# SCH.net
KiCad netlist of a schematic drawn in EAGLE
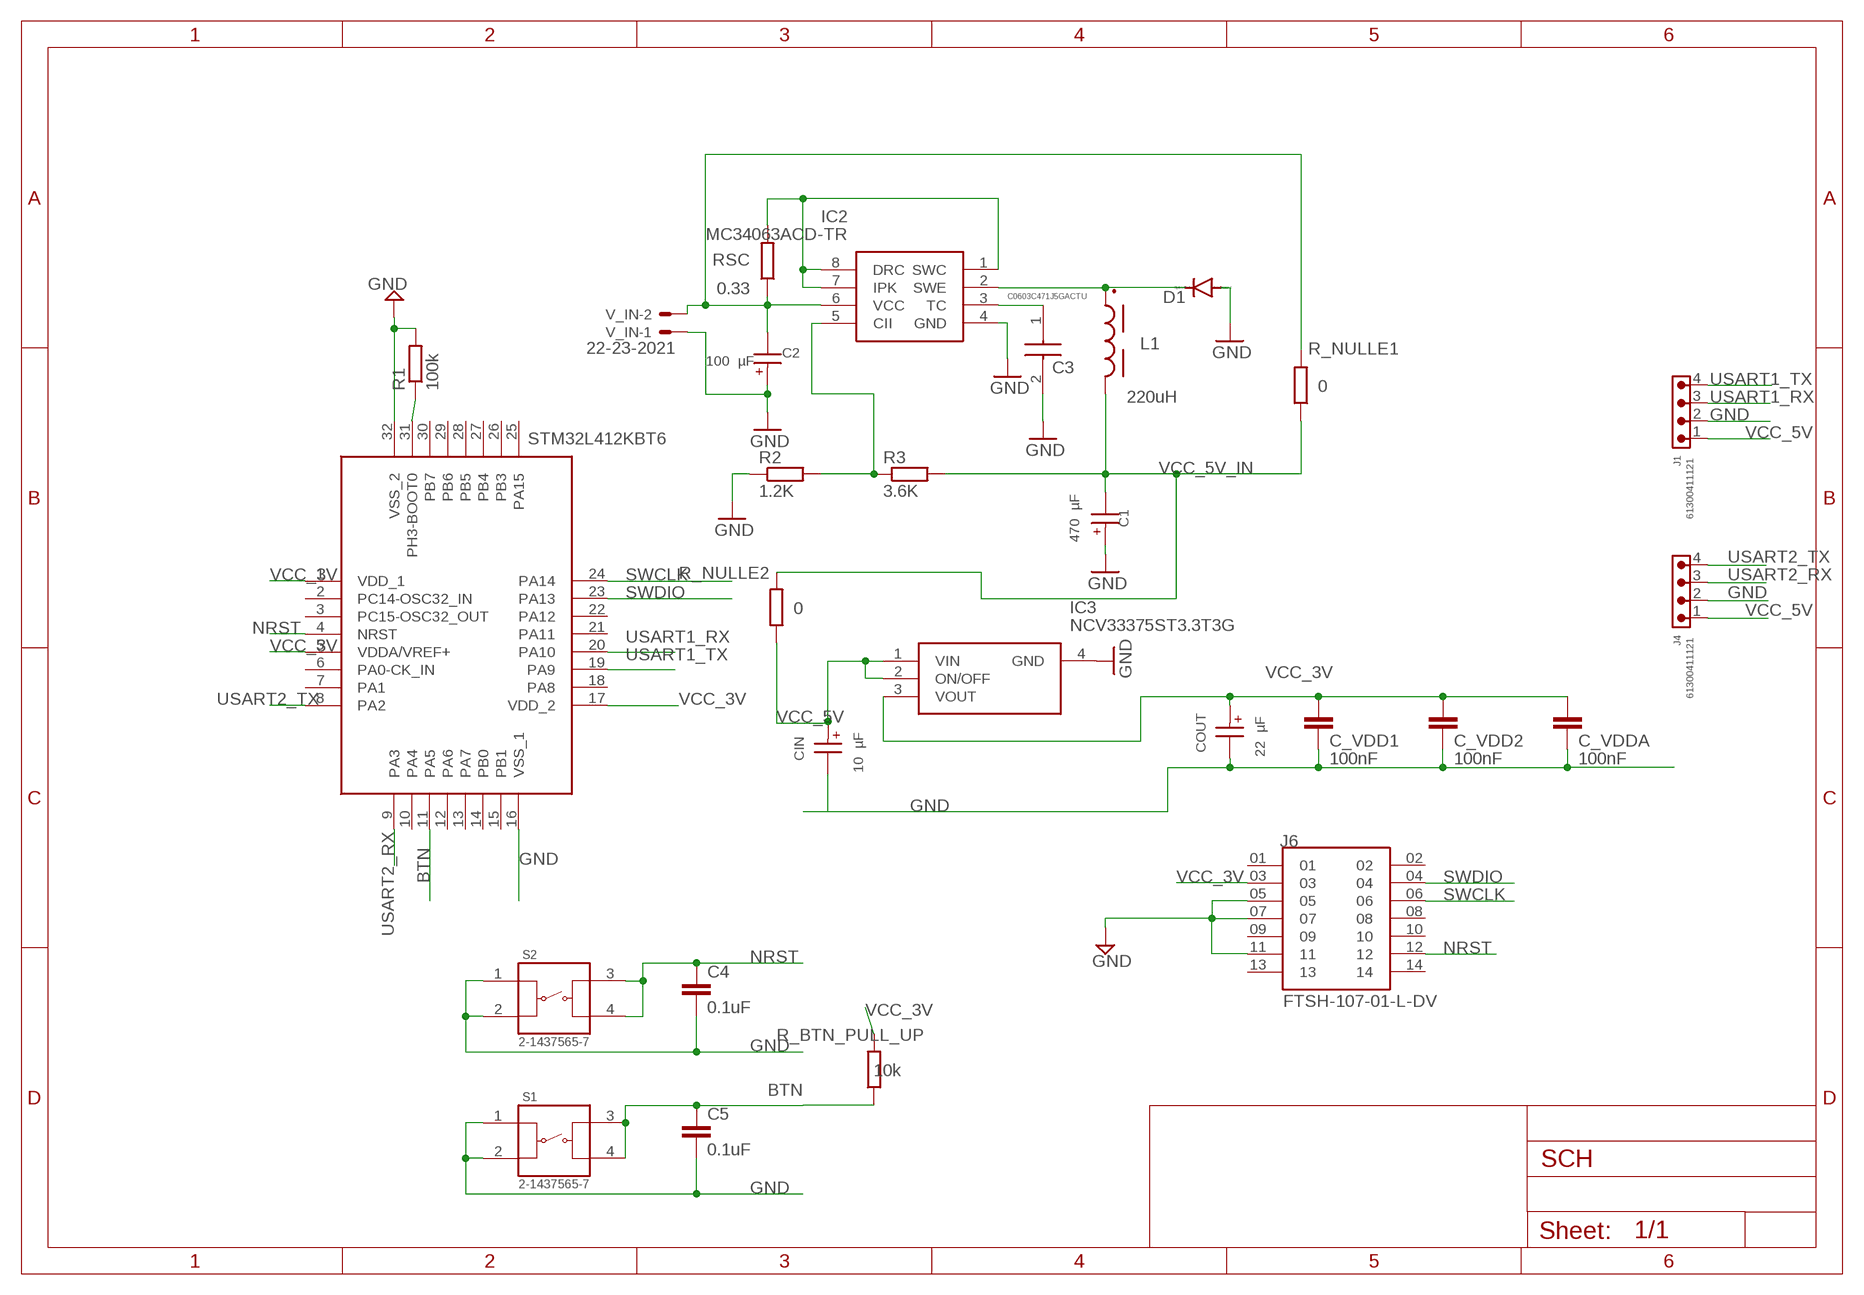
[diagram p0: schematic, sheet 1]

(export (version "E")
  (design (tool "Eeschema 10.0.6"))
  (components
    (comp (ref "C1")
      (value "470 µF")
      (footprint "eagle-import:WCAP-ASLL_8X10.5(DXL)")
      (libsource (lib "eagle-import") (part "WCAP-ASLL_8X10.5_865060353009"))
    )
    (comp (ref "C2")
      (value "100 µF")
      (footprint "eagle-import:WCAP-ASLL_6.3X7.7(DXL)")
      (libsource (lib "eagle-import") (part "WCAP-ASLL_6.3X7.7_865060445005"))
    )
    (comp (ref "C3")
      (value "C0603C471J5GACTU")
      (footprint "eagle-import:C0603")
      (fields (field (name "MOUSER_PART_NUMBER") "80-C0603C471J5G"))
      (libsource (lib "eagle-import") (part "C0603C471J5GACTU"))
    )
    (comp (ref "C4")
      (value "0.1uF")
      (footprint "eagle-import:C0603")
      (libsource (lib "eagle-import") (part "C-EUC0603"))
    )
    (comp (ref "C5")
      (value "0.1uF")
      (footprint "eagle-import:C0603")
      (libsource (lib "eagle-import") (part "C-EUC0603"))
    )
    (comp (ref "CIN")
      (value "10 µF")
      (footprint "eagle-import:WCAP-ASLL_4X5.5(DXL)")
      (libsource (lib "eagle-import") (part "WCAP-ASLL_4X5.5_865060440001"))
    )
    (comp (ref "COUT")
      (value "22 µF")
      (footprint "eagle-import:WCAP-ASLL_5X5.5(DXL)")
      (libsource (lib "eagle-import") (part "WCAP-ASLL_5X5.5_865060442002"))
    )
    (comp (ref "C_VDD1")
      (value "100nF")
      (footprint "eagle-import:C0603")
      (libsource (lib "eagle-import") (part "C-EUC0603"))
    )
    (comp (ref "C_VDD2")
      (value "100nF")
      (footprint "eagle-import:C0603")
      (libsource (lib "eagle-import") (part "C-EUC0603"))
    )
    (comp (ref "C_VDDA")
      (value "100nF")
      (footprint "eagle-import:C0603")
      (libsource (lib "eagle-import") (part "C-EUC0603"))
    )
    (comp (ref "D1")
      (value "DIODE-DO214AC")
      (footprint "eagle-import:DO214AC")
      (libsource (lib "eagle-import") (part "DIODE-DO214AC"))
    )
    (comp (ref "IC1")
      (value "STM32L412KBT6")
      (footprint "eagle-import:QFP80P900X900X160-32N")
      (fields (field (name "MOUSER_PART_NUMBER") "511-STM32L412KBT6"))
      (libsource (lib "eagle-import") (part "STM32L412KBT6"))
    )
    (comp (ref "IC2")
      (value "MC34063ACD-TR")
      (footprint "eagle-import:SOIC127P600X175-8N")
      (fields (field (name "MOUSER_PART_NUMBER") "511-MC34063ACD-TR"))
      (libsource (lib "eagle-import") (part "MC34063ACD-TR"))
    )
    (comp (ref "IC3")
      (value "NCV33375ST3.3T3G")
      (footprint "eagle-import:SOT230P700X175-4N")
      (fields (field (name "MOUSER_PART_NUMBER") "863-NCV33375ST3.3T3G"))
      (libsource (lib "eagle-import") (part "NCV33375ST3.3T3G"))
    )
    (comp (ref "J1")
      (value "61300411121")
      (footprint "eagle-import:61300411121")
      (libsource (lib "eagle-import") (part "6130XX11121_61300411121"))
    )
    (comp (ref "J4")
      (value "61300411121")
      (footprint "eagle-import:61300411121")
      (libsource (lib "eagle-import") (part "6130XX11121_61300411121"))
    )
    (comp (ref "J6")
      (value "FTSH-107-01-L-DV")
      (footprint "eagle-import:SAMTEC_FTSH-107-01-L-DV")
      (fields (field (name "MANUFACTURER") "Samtec"))
      (libsource (lib "eagle-import") (part "FTSH-107-01-L-DV"))
    )
    (comp (ref "L1")
      (value "220uH")
      (footprint "eagle-import:WE-PDA_1260")
      (libsource (lib "eagle-import") (part "WE-PDA_1260_784771221"))
    )
    (comp (ref "R1")
      (value "100k")
      (footprint "eagle-import:R0603")
      (libsource (lib "eagle-import") (part "R-EU_R0603"))
    )
    (comp (ref "R2")
      (value "1.2K")
      (footprint "eagle-import:R0603")
      (libsource (lib "eagle-import") (part "R-EU_R0603"))
    )
    (comp (ref "R3")
      (value "3.6K")
      (footprint "eagle-import:R0603")
      (libsource (lib "eagle-import") (part "R-EU_R0603"))
    )
    (comp (ref "RSC")
      (value "0.33")
      (footprint "eagle-import:R1206W")
      (libsource (lib "eagle-import") (part "R-EU_R1206W"))
    )
    (comp (ref "R_BTN_PULL_UP")
      (value "10k")
      (footprint "eagle-import:R0603")
      (libsource (lib "eagle-import") (part "R-EU_R0603"))
    )
    (comp (ref "R_NULLE1")
      (value "0")
      (footprint "eagle-import:R0603")
      (libsource (lib "eagle-import") (part "R-EU_R0603"))
    )
    (comp (ref "R_NULLE2")
      (value "0")
      (footprint "eagle-import:R0603")
      (libsource (lib "eagle-import") (part "R-EU_R0603"))
    )
    (comp (ref "S1")
      (value "2-1437565-7")
      (footprint "eagle-import:SW_2-1437565-7")
      (fields (field (name "MF") "TE Connectivity") (field (name "MP") "FSM2JSMA"))
      (libsource (lib "eagle-import") (part "2-1437565-7"))
    )
    (comp (ref "S2")
      (value "2-1437565-7")
      (footprint "eagle-import:SW_2-1437565-7")
      (fields (field (name "MF") "TE Connectivity") (field (name "MP") "FSM2JSMA"))
      (libsource (lib "eagle-import") (part "2-1437565-7"))
    )
    (comp (ref "V_IN")
      (value "22-23-2021")
      (footprint "eagle-import:22-23-2021")
      (fields (field (name "MF") "MOLEX"))
      (libsource (lib "eagle-import") (part "22-23-2021"))
    )
  )
  (nets
    (net (code "1") (name "/BTN") (class "Default")
      (node (ref "C5") (pin "1") (pinfunction "1_1") (pintype "passive"))
      (node (ref "IC1") (pin "11") (pinfunction "PA5_11") (pintype "bidirectional"))
      (node (ref "R_BTN_PULL_UP") (pin "1") (pinfunction "1_1") (pintype "passive"))
      (node (ref "S1") (pin "3") (pinfunction "3_3") (pintype "passive"))
      (node (ref "S1") (pin "4") (pinfunction "4_4") (pintype "passive"))
    )
    (net (code "2") (name "/NRST") (class "Default")
      (node (ref "C4") (pin "1") (pinfunction "1_1") (pintype "passive"))
      (node (ref "IC1") (pin "4") (pinfunction "NRST_4") (pintype "input"))
      (node (ref "J6") (pin "12") (pinfunction "12_12") (pintype "passive"))
      (node (ref "S2") (pin "3") (pinfunction "3_3") (pintype "passive"))
      (node (ref "S2") (pin "4") (pinfunction "4_4") (pintype "passive"))
    )
    (net (code "3") (name "/SWCLK") (class "Default")
      (node (ref "IC1") (pin "24") (pinfunction "PA14_24") (pintype "bidirectional"))
      (node (ref "J6") (pin "06") (pinfunction "06_06") (pintype "passive"))
    )
    (net (code "4") (name "/SWDIO") (class "Default")
      (node (ref "IC1") (pin "23") (pinfunction "PA13_23") (pintype "bidirectional"))
      (node (ref "J6") (pin "04") (pinfunction "04_04") (pintype "passive"))
    )
    (net (code "5") (name "/USART1_RX") (class "Default")
      (node (ref "IC1") (pin "20") (pinfunction "PA10_20") (pintype "bidirectional"))
      (node (ref "J1") (pin "3") (pinfunction "3_3") (pintype "passive"))
    )
    (net (code "6") (name "/USART1_TX") (class "Default")
      (node (ref "IC1") (pin "19") (pinfunction "PA9_19") (pintype "bidirectional"))
      (node (ref "J1") (pin "4") (pinfunction "4_4") (pintype "passive"))
    )
    (net (code "7") (name "/USART2_RX") (class "Default")
      (node (ref "IC1") (pin "9") (pinfunction "PA3_9") (pintype "bidirectional"))
      (node (ref "J4") (pin "3") (pinfunction "3_3") (pintype "passive"))
    )
    (net (code "8") (name "/USART2_TX") (class "Default")
      (node (ref "IC1") (pin "8") (pinfunction "PA2_8") (pintype "bidirectional"))
      (node (ref "J4") (pin "4") (pinfunction "4_4") (pintype "passive"))
    )
    (net (code "9") (name "/VCC_3V") (class "Default")
      (node (ref "COUT") (pin "1") (pinfunction "+_1") (pintype "passive"))
      (node (ref "C_VDD1") (pin "1") (pinfunction "1_1") (pintype "passive"))
      (node (ref "C_VDD2") (pin "1") (pinfunction "1_1") (pintype "passive"))
      (node (ref "C_VDDA") (pin "1") (pinfunction "1_1") (pintype "passive"))
      (node (ref "IC1") (pin "1") (pinfunction "VDD_1_1") (pintype "power_in"))
      (node (ref "IC1") (pin "17") (pinfunction "VDD_2_17") (pintype "power_in"))
      (node (ref "IC1") (pin "5") (pinfunction "VDDA/VREF+_5") (pintype "power_in"))
      (node (ref "IC3") (pin "3") (pinfunction "VOUT_3") (pintype "bidirectional"))
      (node (ref "J6") (pin "03") (pinfunction "03_03") (pintype "passive"))
      (node (ref "R_BTN_PULL_UP") (pin "2") (pinfunction "2_2") (pintype "passive"))
    )
    (net (code "10") (name "/VCC_5V") (class "Default")
      (node (ref "CIN") (pin "1") (pinfunction "+_1") (pintype "passive"))
      (node (ref "IC3") (pin "1") (pinfunction "VIN_1") (pintype "bidirectional"))
      (node (ref "IC3") (pin "2") (pinfunction "ON/OFF_2") (pintype "bidirectional"))
      (node (ref "J1") (pin "1") (pinfunction "1_1") (pintype "passive"))
      (node (ref "J4") (pin "1") (pinfunction "1_1") (pintype "passive"))
      (node (ref "R_NULLE2") (pin "1") (pinfunction "1_1") (pintype "passive"))
    )
    (net (code "11") (name "/VCC_5V_IN") (class "Default")
      (node (ref "C1") (pin "2") (pinfunction "-_2") (pintype "passive"))
      (node (ref "L1") (pin "2") (pinfunction "2_2") (pintype "passive"))
      (node (ref "R3") (pin "2") (pinfunction "2_2") (pintype "passive"))
      (node (ref "R_NULLE1") (pin "1") (pinfunction "1_1") (pintype "passive"))
      (node (ref "R_NULLE2") (pin "2") (pinfunction "2_2") (pintype "passive"))
    )
    (net (code "12") (name "GND") (class "Default")
      (node (ref "C1") (pin "1") (pinfunction "+_1") (pintype "passive"))
      (node (ref "C2") (pin "1") (pinfunction "+_1") (pintype "passive"))
      (node (ref "C3") (pin "2") (pinfunction "2_2") (pintype "bidirectional"))
      (node (ref "C4") (pin "2") (pinfunction "2_2") (pintype "passive"))
      (node (ref "C5") (pin "2") (pinfunction "2_2") (pintype "passive"))
      (node (ref "CIN") (pin "2") (pinfunction "-_2") (pintype "passive"))
      (node (ref "COUT") (pin "2") (pinfunction "-_2") (pintype "passive"))
      (node (ref "C_VDD1") (pin "2") (pinfunction "2_2") (pintype "passive"))
      (node (ref "C_VDD2") (pin "2") (pinfunction "2_2") (pintype "passive"))
      (node (ref "C_VDDA") (pin "2") (pinfunction "2_2") (pintype "passive"))
      (node (ref "D1") (pin "A") (pinfunction "A_A") (pintype "passive"))
      (node (ref "IC1") (pin "16") (pinfunction "VSS_1_16") (pintype "power_in"))
      (node (ref "IC1") (pin "32") (pinfunction "VSS_2_32") (pintype "power_in"))
      (node (ref "IC2") (pin "4") (pinfunction "GND_4") (pintype "bidirectional"))
      (node (ref "IC3") (pin "4") (pinfunction "GND_4") (pintype "bidirectional"))
      (node (ref "J1") (pin "2") (pinfunction "2_2") (pintype "passive"))
      (node (ref "J4") (pin "2") (pinfunction "2_2") (pintype "passive"))
      (node (ref "J6") (pin "05") (pinfunction "05_05") (pintype "passive"))
      (node (ref "J6") (pin "07") (pinfunction "07_07") (pintype "passive"))
      (node (ref "J6") (pin "11") (pinfunction "11_11") (pintype "passive"))
      (node (ref "R1") (pin "2") (pinfunction "2_2") (pintype "passive"))
      (node (ref "R2") (pin "1") (pinfunction "1_1") (pintype "passive"))
      (node (ref "S1") (pin "1") (pinfunction "1_1") (pintype "passive"))
      (node (ref "S1") (pin "2") (pinfunction "2_2") (pintype "passive"))
      (node (ref "S2") (pin "1") (pinfunction "1_1") (pintype "passive"))
      (node (ref "S2") (pin "2") (pinfunction "2_2") (pintype "passive"))
      (node (ref "V_IN") (pin "1") (pinfunction "S_1") (pintype "passive"))
    )
    (net (code "13") (name "Net-(C2--)") (class "Default")
      (node (ref "C2") (pin "2") (pinfunction "-_2") (pintype "passive"))
      (node (ref "IC2") (pin "6") (pinfunction "VCC_6") (pintype "bidirectional"))
      (node (ref "RSC") (pin "1") (pinfunction "1_1") (pintype "passive"))
      (node (ref "R_NULLE1") (pin "2") (pinfunction "2_2") (pintype "passive"))
      (node (ref "V_IN") (pin "2") (pinfunction "S_2") (pintype "passive"))
    )
    (net (code "14") (name "Net-(IC1-PH3-BOOT0)") (class "Default")
      (node (ref "IC1") (pin "31") (pinfunction "PH3-BOOT0_31") (pintype "bidirectional"))
      (node (ref "R1") (pin "1") (pinfunction "1_1") (pintype "passive"))
    )
    (net (code "15") (name "Net-(IC2-CII)") (class "Default")
      (node (ref "IC2") (pin "5") (pinfunction "CII_5") (pintype "bidirectional"))
      (node (ref "R2") (pin "2") (pinfunction "2_2") (pintype "passive"))
      (node (ref "R3") (pin "1") (pinfunction "1_1") (pintype "passive"))
    )
    (net (code "16") (name "Net-(IC2-DRC)") (class "Default")
      (node (ref "IC2") (pin "1") (pinfunction "SWC_1") (pintype "bidirectional"))
      (node (ref "IC2") (pin "7") (pinfunction "IPK_7") (pintype "bidirectional"))
      (node (ref "IC2") (pin "8") (pinfunction "DRC_8") (pintype "bidirectional"))
      (node (ref "RSC") (pin "2") (pinfunction "2_2") (pintype "passive"))
    )
    (net (code "17") (name "Net-(IC2-SWE)") (class "Default")
      (node (ref "D1") (pin "C") (pinfunction "C_C") (pintype "passive"))
      (node (ref "IC2") (pin "2") (pinfunction "SWE_2") (pintype "bidirectional"))
      (node (ref "L1") (pin "1") (pinfunction "1_1") (pintype "passive"))
    )
    (net (code "18") (name "Net-(IC2-TC)") (class "Default")
      (node (ref "C3") (pin "1") (pinfunction "1_1") (pintype "bidirectional"))
      (node (ref "IC2") (pin "3") (pinfunction "TC_3") (pintype "bidirectional"))
    )
    (net (code "19") (name "unconnected-(IC1-PA0-CK_IN-Pad6)") (class "Default")
      (node (ref "IC1") (pin "6") (pinfunction "PA0-CK_IN_6") (pintype "bidirectional"))
    )
    (net (code "20") (name "unconnected-(IC1-PA1-Pad7)") (class "Default")
      (node (ref "IC1") (pin "7") (pinfunction "PA1_7") (pintype "bidirectional"))
    )
    (net (code "21") (name "unconnected-(IC1-PA4-Pad10)") (class "Default")
      (node (ref "IC1") (pin "10") (pinfunction "PA4_10") (pintype "bidirectional"))
    )
    (net (code "22") (name "unconnected-(IC1-PA6-Pad12)") (class "Default")
      (node (ref "IC1") (pin "12") (pinfunction "PA6_12") (pintype "bidirectional"))
    )
    (net (code "23") (name "unconnected-(IC1-PA7-Pad13)") (class "Default")
      (node (ref "IC1") (pin "13") (pinfunction "PA7_13") (pintype "bidirectional"))
    )
    (net (code "24") (name "unconnected-(IC1-PA8-Pad18)") (class "Default")
      (node (ref "IC1") (pin "18") (pinfunction "PA8_18") (pintype "bidirectional"))
    )
    (net (code "25") (name "unconnected-(IC1-PA11-Pad21)") (class "Default")
      (node (ref "IC1") (pin "21") (pinfunction "PA11_21") (pintype "bidirectional"))
    )
    (net (code "26") (name "unconnected-(IC1-PA12-Pad22)") (class "Default")
      (node (ref "IC1") (pin "22") (pinfunction "PA12_22") (pintype "bidirectional"))
    )
    (net (code "27") (name "unconnected-(IC1-PA15-Pad25)") (class "Default")
      (node (ref "IC1") (pin "25") (pinfunction "PA15_25") (pintype "bidirectional"))
    )
    (net (code "28") (name "unconnected-(IC1-PB0-Pad14)") (class "Default")
      (node (ref "IC1") (pin "14") (pinfunction "PB0_14") (pintype "bidirectional"))
    )
    (net (code "29") (name "unconnected-(IC1-PB1-Pad15)") (class "Default")
      (node (ref "IC1") (pin "15") (pinfunction "PB1_15") (pintype "bidirectional"))
    )
    (net (code "30") (name "unconnected-(IC1-PB3-Pad26)") (class "Default")
      (node (ref "IC1") (pin "26") (pinfunction "PB3_26") (pintype "bidirectional"))
    )
    (net (code "31") (name "unconnected-(IC1-PB4-Pad27)") (class "Default")
      (node (ref "IC1") (pin "27") (pinfunction "PB4_27") (pintype "bidirectional"))
    )
    (net (code "32") (name "unconnected-(IC1-PB5-Pad28)") (class "Default")
      (node (ref "IC1") (pin "28") (pinfunction "PB5_28") (pintype "bidirectional"))
    )
    (net (code "33") (name "unconnected-(IC1-PB6-Pad29)") (class "Default")
      (node (ref "IC1") (pin "29") (pinfunction "PB6_29") (pintype "bidirectional"))
    )
    (net (code "34") (name "unconnected-(IC1-PB7-Pad30)") (class "Default")
      (node (ref "IC1") (pin "30") (pinfunction "PB7_30") (pintype "bidirectional"))
    )
    (net (code "35") (name "unconnected-(IC1-PC14-OSC32_IN-Pad2)") (class "Default")
      (node (ref "IC1") (pin "2") (pinfunction "PC14-OSC32_IN_2") (pintype "bidirectional"))
    )
    (net (code "36") (name "unconnected-(IC1-PC15-OSC32_OUT-Pad3)") (class "Default")
      (node (ref "IC1") (pin "3") (pinfunction "PC15-OSC32_OUT_3") (pintype "bidirectional"))
    )
    (net (code "37") (name "unconnected-(J6-Pad01)") (class "Default")
      (node (ref "J6") (pin "01") (pinfunction "01_01") (pintype "passive"))
    )
    (net (code "38") (name "unconnected-(J6-Pad02)") (class "Default")
      (node (ref "J6") (pin "02") (pinfunction "02_02") (pintype "passive"))
    )
    (net (code "39") (name "unconnected-(J6-Pad08)") (class "Default")
      (node (ref "J6") (pin "08") (pinfunction "08_08") (pintype "passive"))
    )
    (net (code "40") (name "unconnected-(J6-Pad09)") (class "Default")
      (node (ref "J6") (pin "09") (pinfunction "09_09") (pintype "passive"))
    )
    (net (code "41") (name "unconnected-(J6-Pad10)") (class "Default")
      (node (ref "J6") (pin "10") (pinfunction "10_10") (pintype "passive"))
    )
    (net (code "42") (name "unconnected-(J6-Pad13)") (class "Default")
      (node (ref "J6") (pin "13") (pinfunction "13_13") (pintype "passive"))
    )
    (net (code "43") (name "unconnected-(J6-Pad14)") (class "Default")
      (node (ref "J6") (pin "14") (pinfunction "14_14") (pintype "passive"))
    )
  )
)
